# schematic1.net
KiCad netlist of a schematic drawn in EAGLE
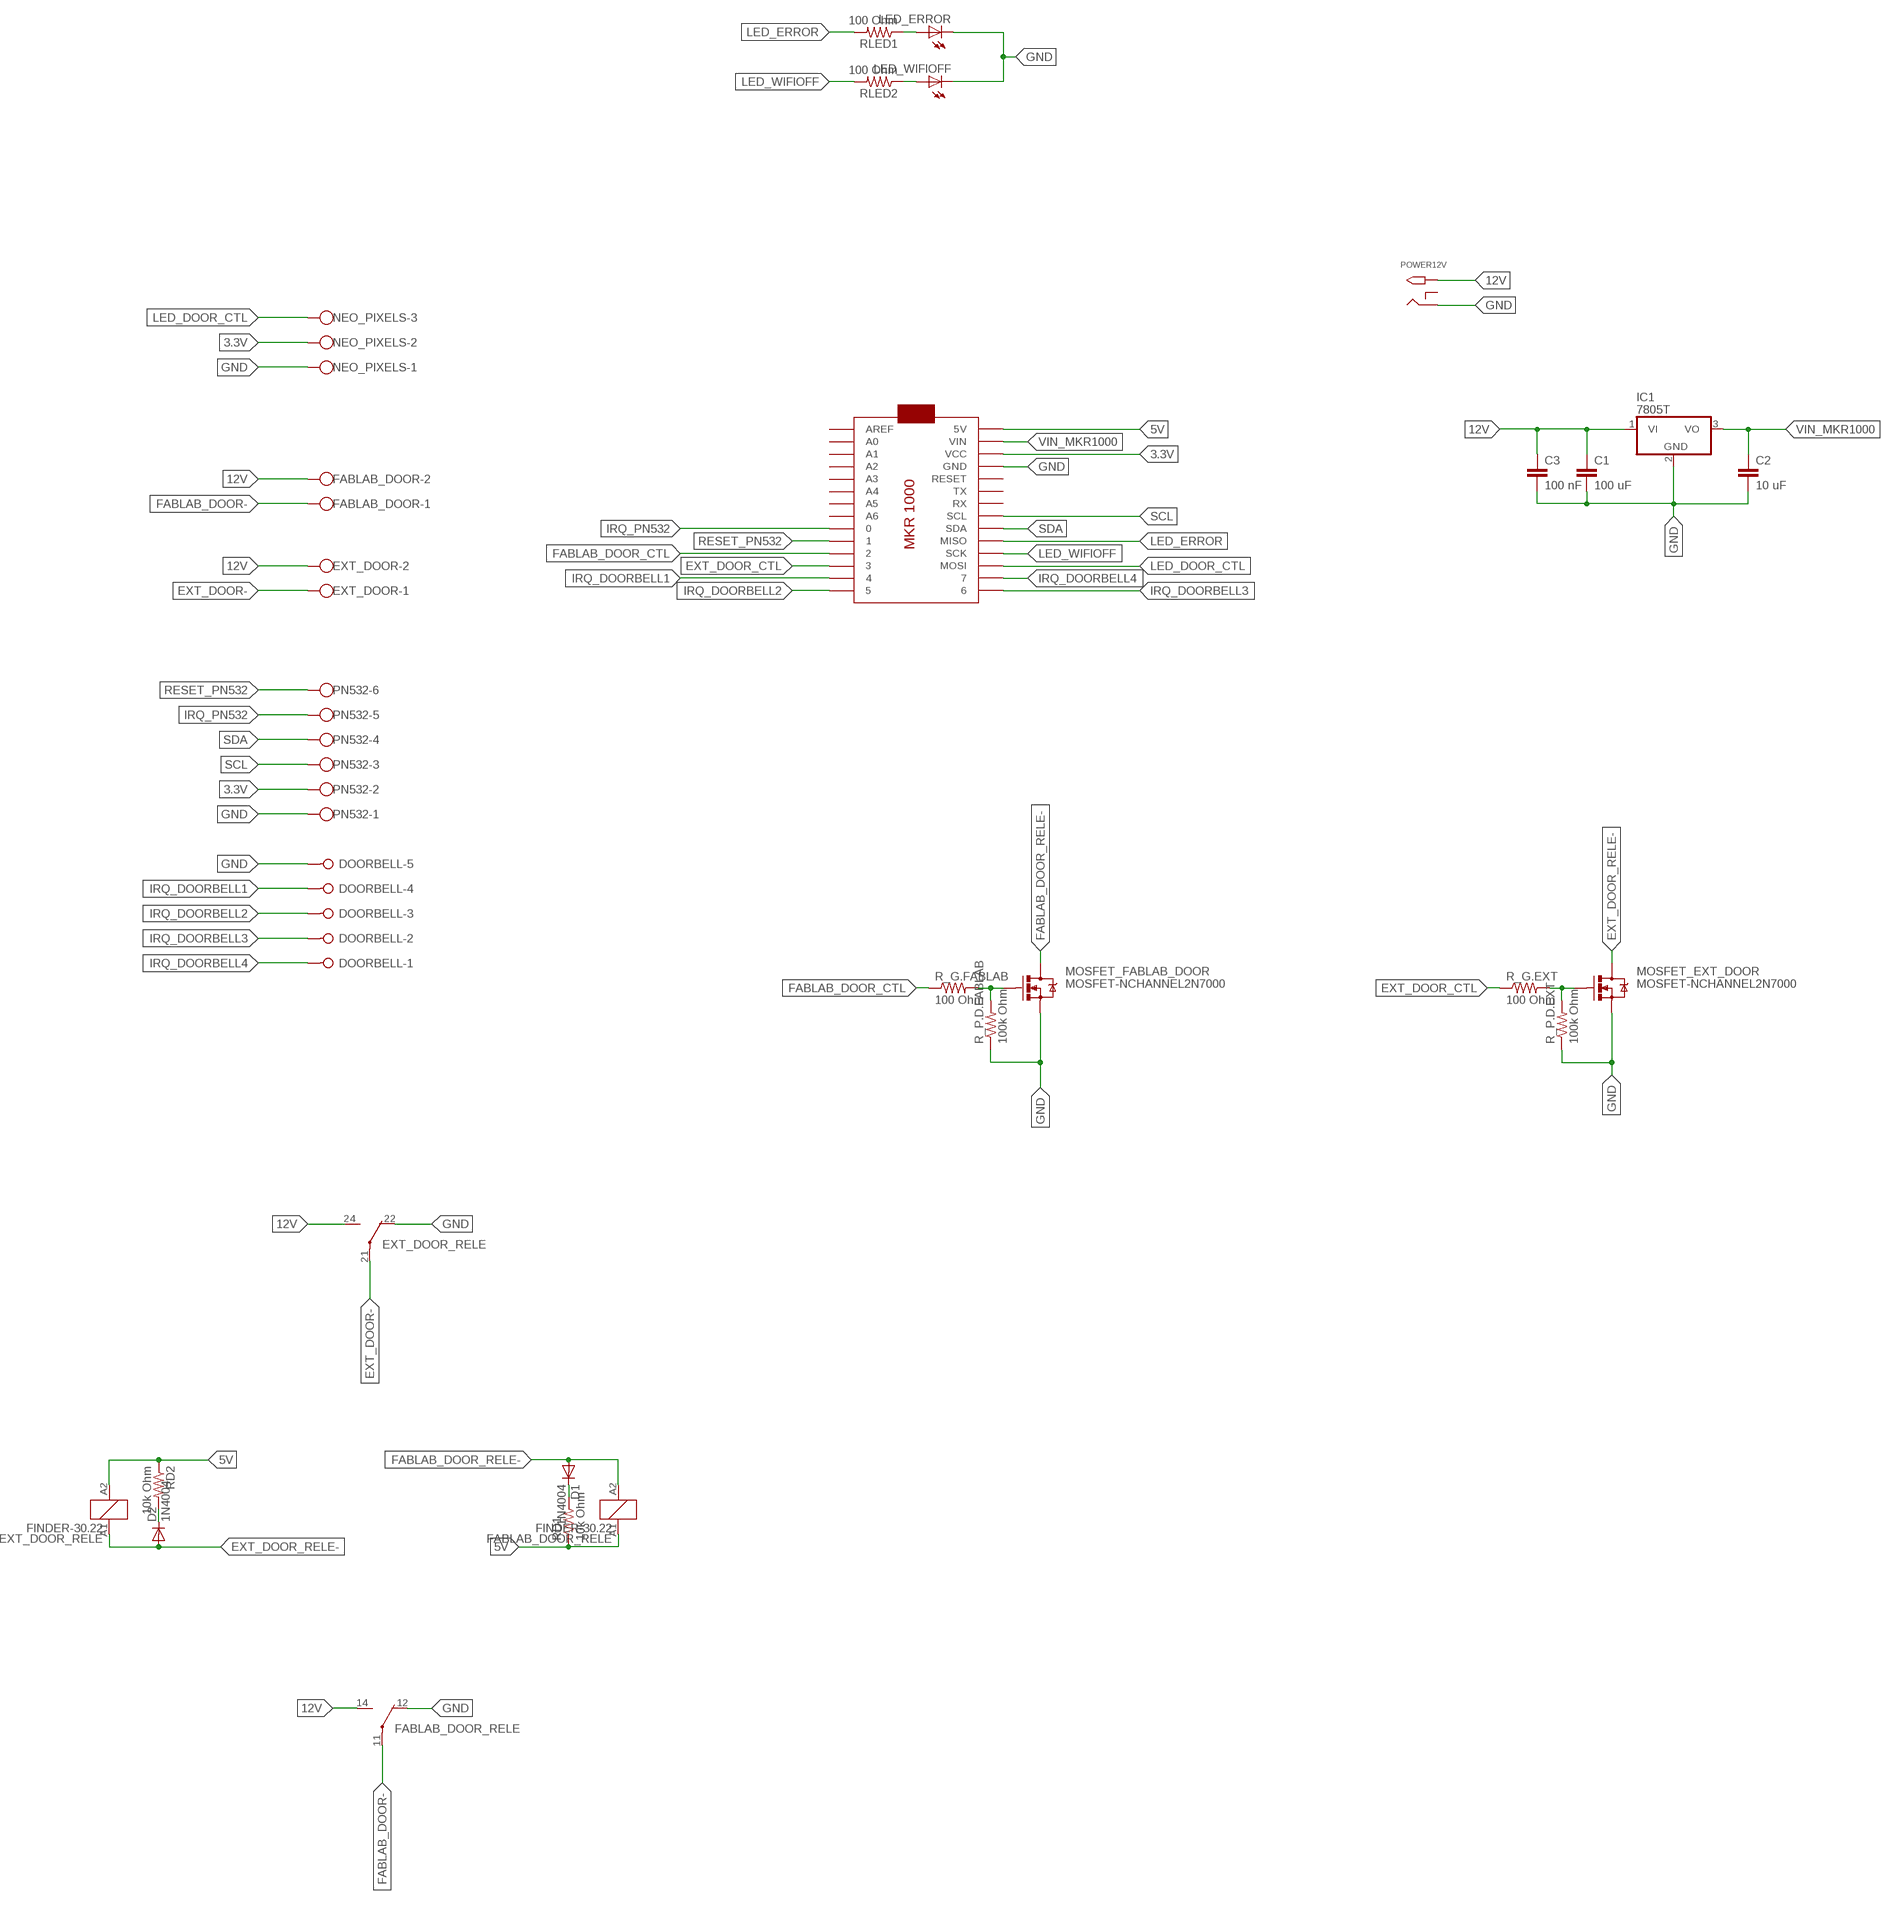
[diagram p0: schematic, sheet 1]

(export (version "E")
  (design (tool "Eeschema 10.0.6"))
  (components
    (comp (ref "C1")
      (value "100 uF")
      (footprint "eagle-import:C2.5-2")
      (libsource (lib "eagle-import") (part "C2.5/2"))
    )
    (comp (ref "C2")
      (value "10 uF")
      (footprint "eagle-import:C2.5-2")
      (libsource (lib "eagle-import") (part "C2.5/2"))
    )
    (comp (ref "C3")
      (value "100 nF")
      (footprint "eagle-import:C2.5-2")
      (libsource (lib "eagle-import") (part "C2.5/2"))
    )
    (comp (ref "D1")
      (value "1N4004")
      (footprint "eagle-import:DO41-10")
      (libsource (lib "eagle-import") (part "1N4004"))
    )
    (comp (ref "D2")
      (value "1N4004")
      (footprint "eagle-import:DO41-10")
      (libsource (lib "eagle-import") (part "1N4004"))
    )
    (comp (ref "DOORBELL")
      (value "W237-05P")
      (footprint "eagle-import:W237-5P")
      (libsource (lib "eagle-import") (part "W237-05P"))
    )
    (comp (ref "EXT_DOOR")
      (value "W237-102")
      (footprint "eagle-import:W237-102")
      (fields (field (name "MPN") "237-102"))
      (libsource (lib "eagle-import") (part "W237-102"))
    )
    (comp (ref "EXT_DOOR_RELE")
      (value "FINDER-30.22")
      (footprint "eagle-import:FINDER-30.22")
      (libsource (lib "eagle-import") (part "FINDER-30.22"))
    )
    (comp (ref "FABLAB_DOOR")
      (value "W237-102")
      (footprint "eagle-import:W237-102")
      (fields (field (name "MPN") "237-102"))
      (libsource (lib "eagle-import") (part "W237-102"))
    )
    (comp (ref "FABLAB_DOOR_RELE")
      (value "FINDER-30.22")
      (footprint "eagle-import:FINDER-30.22")
      (libsource (lib "eagle-import") (part "FINDER-30.22"))
    )
    (comp (ref "IC1")
      (value "7805T")
      (footprint "eagle-import:TO220H")
      (libsource (lib "eagle-import") (part "78T05"))
    )
    (comp (ref "LED_ERROR")
      (value "LED3MM")
      (footprint "eagle-import:LED3MM")
      (libsource (lib "eagle-import") (part "LED3MM"))
    )
    (comp (ref "LED_WIFIOFF")
      (value "LED3MM")
      (footprint "eagle-import:LED3MM")
      (libsource (lib "eagle-import") (part "LED3MM"))
    )
    (comp (ref "MOSFET_EXT_DOOR")
      (value "MOSFET-NCHANNEL2N7000")
      (footprint "eagle-import:TO-92")
      (libsource (lib "eagle-import") (part "MOSFET-NCHANNEL2N7000"))
    )
    (comp (ref "MOSFET_FABLAB_DOOR")
      (value "MOSFET-NCHANNEL2N7000")
      (footprint "eagle-import:TO-92")
      (libsource (lib "eagle-import") (part "MOSFET-NCHANNEL2N7000"))
    )
    (comp (ref "NEO_PIXELS")
      (value "W237-103")
      (footprint "eagle-import:W237-103")
      (fields (field (name "MPN") "237-103"))
      (libsource (lib "eagle-import") (part "W237-103"))
    )
    (comp (ref "PN532")
      (value "W237-136")
      (footprint "eagle-import:W237-136")
      (fields (field (name "MPN") "237-136"))
      (libsource (lib "eagle-import") (part "W237-136"))
    )
    (comp (ref "POWER12V")
      (value "2.1MMJACKTHM")
      (footprint "eagle-import:PJ-102A")
      (libsource (lib "eagle-import") (part "2.1MMJACKTHM"))
    )
    (comp (ref "RD1")
      (value "10k Ohm")
      (footprint "eagle-import:0207_10")
      (libsource (lib "eagle-import") (part "R-US_0207/10"))
    )
    (comp (ref "RD2")
      (value "10k Ohm")
      (footprint "eagle-import:0207_10")
      (libsource (lib "eagle-import") (part "R-US_0207/10"))
    )
    (comp (ref "RLED1")
      (value "100 Ohm")
      (footprint "eagle-import:0207_10")
      (libsource (lib "eagle-import") (part "R-US_0207/10"))
    )
    (comp (ref "RLED2")
      (value "100 Ohm")
      (footprint "eagle-import:0207_10")
      (libsource (lib "eagle-import") (part "R-US_0207/10"))
    )
    (comp (ref "R_G.EXT")
      (value "100 Ohm")
      (footprint "eagle-import:0207_10")
      (libsource (lib "eagle-import") (part "R-US_0207/10"))
    )
    (comp (ref "R_G.FABLAB")
      (value "100 Ohm")
      (footprint "eagle-import:0207_10")
      (libsource (lib "eagle-import") (part "R-US_0207/10"))
    )
    (comp (ref "R_P.D.EXT")
      (value "100k Ohm")
      (footprint "eagle-import:0207_10")
      (libsource (lib "eagle-import") (part "R-US_0207/10"))
    )
    (comp (ref "R_P.D.FABLAB")
      (value "100k Ohm")
      (footprint "eagle-import:0207_10")
      (libsource (lib "eagle-import") (part "R-US_0207/10"))
    )
    (comp (ref "U$1")
      (value "ARDUINOMKR1000")
      (footprint "eagle-import:ARDUINOMKR1000")
      (libsource (lib "eagle-import") (part "ARDUINOMKR1000"))
    )
  )
  (nets
    (net (code "1") (name "3.3V") (class "Default")
      (node (ref "NEO_PIXELS") (pin "2") (pinfunction "KL_2") (pintype "passive"))
      (node (ref "PN532") (pin "2") (pinfunction "KL_2") (pintype "passive"))
      (node (ref "U$1") (pin "VCC") (pinfunction "VCC_VCC") (pintype "bidirectional"))
    )
    (net (code "2") (name "5V") (class "Default")
      (node (ref "EXT_DOOR_RELE") (pin "A2") (pinfunction "2_A2") (pintype "passive"))
      (node (ref "FABLAB_DOOR_RELE") (pin "A1") (pinfunction "1_A1") (pintype "passive"))
      (node (ref "RD1") (pin "1") (pinfunction "1_1") (pintype "passive"))
      (node (ref "RD2") (pin "1") (pinfunction "1_1") (pintype "passive"))
      (node (ref "U$1") (pin "5V") (pinfunction "5V_5V") (pintype "bidirectional"))
    )
    (net (code "3") (name "12V") (class "Default")
      (node (ref "C1") (pin "1") (pinfunction "1_1") (pintype "passive"))
      (node (ref "C3") (pin "1") (pinfunction "1_1") (pintype "passive"))
      (node (ref "EXT_DOOR") (pin "2") (pinfunction "KL_2") (pintype "passive"))
      (node (ref "EXT_DOOR_RELE") (pin "24") (pinfunction "S_24") (pintype "passive"))
      (node (ref "FABLAB_DOOR") (pin "2") (pinfunction "KL_2") (pintype "passive"))
      (node (ref "FABLAB_DOOR_RELE") (pin "14") (pinfunction "S_14") (pintype "passive"))
      (node (ref "IC1") (pin "1") (pinfunction "VI_1") (pintype "input"))
      (node (ref "POWER12V") (pin "TIP") (pinfunction "TIP_TIP") (pintype "bidirectional"))
    )
    (net (code "4") (name "EXT_DOOR-") (class "Default")
      (node (ref "EXT_DOOR") (pin "1") (pinfunction "KL_1") (pintype "passive"))
      (node (ref "EXT_DOOR_RELE") (pin "21") (pinfunction "P_21") (pintype "passive"))
    )
    (net (code "5") (name "EXT_DOOR_CTL") (class "Default")
      (node (ref "R_G.EXT") (pin "1") (pinfunction "1_1") (pintype "passive"))
      (node (ref "U$1") (pin "3") (pinfunction "3_3") (pintype "bidirectional"))
    )
    (net (code "6") (name "EXT_DOOR_RELE-") (class "Default")
      (node (ref "D2") (pin "A") (pinfunction "A_A") (pintype "passive"))
      (node (ref "EXT_DOOR_RELE") (pin "A1") (pinfunction "1_A1") (pintype "passive"))
      (node (ref "MOSFET_EXT_DOOR") (pin "3") (pinfunction "D_3") (pintype "passive"))
    )
    (net (code "7") (name "FABLAB_DOOR-") (class "Default")
      (node (ref "FABLAB_DOOR") (pin "1") (pinfunction "KL_1") (pintype "passive"))
      (node (ref "FABLAB_DOOR_RELE") (pin "11") (pinfunction "P_11") (pintype "passive"))
    )
    (net (code "8") (name "FABLAB_DOOR_CTL") (class "Default")
      (node (ref "R_G.FABLAB") (pin "1") (pinfunction "1_1") (pintype "passive"))
      (node (ref "U$1") (pin "2") (pinfunction "2_2") (pintype "bidirectional"))
    )
    (net (code "9") (name "FABLAB_DOOR_RELE-") (class "Default")
      (node (ref "D1") (pin "A") (pinfunction "A_A") (pintype "passive"))
      (node (ref "FABLAB_DOOR_RELE") (pin "A2") (pinfunction "2_A2") (pintype "passive"))
      (node (ref "MOSFET_FABLAB_DOOR") (pin "3") (pinfunction "D_3") (pintype "passive"))
    )
    (net (code "10") (name "GND") (class "Default")
      (node (ref "C1") (pin "2") (pinfunction "2_2") (pintype "passive"))
      (node (ref "C2") (pin "2") (pinfunction "2_2") (pintype "passive"))
      (node (ref "C3") (pin "2") (pinfunction "2_2") (pintype "passive"))
      (node (ref "DOORBELL") (pin "5") (pinfunction "KL_5") (pintype "passive"))
      (node (ref "EXT_DOOR_RELE") (pin "22") (pinfunction "O_22") (pintype "passive"))
      (node (ref "FABLAB_DOOR_RELE") (pin "12") (pinfunction "O_12") (pintype "passive"))
      (node (ref "IC1") (pin "2") (pinfunction "GND_2") (pintype "passive"))
      (node (ref "LED_ERROR") (pin "K") (pinfunction "C_K") (pintype "passive"))
      (node (ref "LED_WIFIOFF") (pin "K") (pinfunction "C_K") (pintype "passive"))
      (node (ref "MOSFET_EXT_DOOR") (pin "1") (pinfunction "S_1") (pintype "passive"))
      (node (ref "MOSFET_FABLAB_DOOR") (pin "1") (pinfunction "S_1") (pintype "passive"))
      (node (ref "NEO_PIXELS") (pin "1") (pinfunction "KL_1") (pintype "passive"))
      (node (ref "PN532") (pin "1") (pinfunction "KL_1") (pintype "passive"))
      (node (ref "POWER12V") (pin "RING") (pinfunction "RING_RING") (pintype "bidirectional"))
      (node (ref "R_P.D.EXT") (pin "1") (pinfunction "1_1") (pintype "passive"))
      (node (ref "R_P.D.FABLAB") (pin "1") (pinfunction "1_1") (pintype "passive"))
      (node (ref "U$1") (pin "GND") (pinfunction "GND_GND") (pintype "bidirectional"))
    )
    (net (code "11") (name "IRQ_DOORBELL1") (class "Default")
      (node (ref "DOORBELL") (pin "4") (pinfunction "KL_4") (pintype "passive"))
      (node (ref "U$1") (pin "4") (pinfunction "4_4") (pintype "bidirectional"))
    )
    (net (code "12") (name "IRQ_DOORBELL2") (class "Default")
      (node (ref "DOORBELL") (pin "3") (pinfunction "KL_3") (pintype "passive"))
      (node (ref "U$1") (pin "5") (pinfunction "5_5") (pintype "bidirectional"))
    )
    (net (code "13") (name "IRQ_DOORBELL3") (class "Default")
      (node (ref "DOORBELL") (pin "2") (pinfunction "KL_2") (pintype "passive"))
      (node (ref "U$1") (pin "6") (pinfunction "6_6") (pintype "bidirectional"))
    )
    (net (code "14") (name "IRQ_DOORBELL4") (class "Default")
      (node (ref "DOORBELL") (pin "1") (pinfunction "KL_1") (pintype "passive"))
      (node (ref "U$1") (pin "7") (pinfunction "7_7") (pintype "bidirectional"))
    )
    (net (code "15") (name "IRQ_PN532") (class "Default")
      (node (ref "PN532") (pin "5") (pinfunction "KL_5") (pintype "passive"))
      (node (ref "U$1") (pin "0") (pinfunction "0_0") (pintype "bidirectional"))
    )
    (net (code "16") (name "LED_DOOR_CTL") (class "Default")
      (node (ref "NEO_PIXELS") (pin "3") (pinfunction "KL_3") (pintype "passive"))
      (node (ref "U$1") (pin "MOSI") (pinfunction "MOSI_MOSI") (pintype "bidirectional"))
    )
    (net (code "17") (name "LED_ERROR") (class "Default")
      (node (ref "RLED1") (pin "2") (pinfunction "2_2") (pintype "passive"))
      (node (ref "U$1") (pin "MISO") (pinfunction "MISO_MISO") (pintype "bidirectional"))
    )
    (net (code "18") (name "LED_WIFIOFF") (class "Default")
      (node (ref "RLED2") (pin "2") (pinfunction "2_2") (pintype "passive"))
      (node (ref "U$1") (pin "SCK") (pinfunction "SCK_SCK") (pintype "bidirectional"))
    )
    (net (code "19") (name "Net-(D1-PadC)") (class "Default")
      (node (ref "D1") (pin "C") (pinfunction "C_C") (pintype "passive"))
      (node (ref "RD1") (pin "2") (pinfunction "2_2") (pintype "passive"))
    )
    (net (code "20") (name "Net-(D2-PadC)") (class "Default")
      (node (ref "D2") (pin "C") (pinfunction "C_C") (pintype "passive"))
      (node (ref "RD2") (pin "2") (pinfunction "2_2") (pintype "passive"))
    )
    (net (code "21") (name "Net-(LED_ERROR-PadA)") (class "Default")
      (node (ref "LED_ERROR") (pin "A") (pinfunction "A_A") (pintype "passive"))
      (node (ref "RLED1") (pin "1") (pinfunction "1_1") (pintype "passive"))
    )
    (net (code "22") (name "Net-(LED_WIFIOFF-PadA)") (class "Default")
      (node (ref "LED_WIFIOFF") (pin "A") (pinfunction "A_A") (pintype "passive"))
      (node (ref "RLED2") (pin "1") (pinfunction "1_1") (pintype "passive"))
    )
    (net (code "23") (name "Net-(MOSFET_EXT_DOOR-G)") (class "Default")
      (node (ref "MOSFET_EXT_DOOR") (pin "2") (pinfunction "G_2") (pintype "passive"))
      (node (ref "R_G.EXT") (pin "2") (pinfunction "2_2") (pintype "passive"))
      (node (ref "R_P.D.EXT") (pin "2") (pinfunction "2_2") (pintype "passive"))
    )
    (net (code "24") (name "Net-(MOSFET_FABLAB_DOOR-G)") (class "Default")
      (node (ref "MOSFET_FABLAB_DOOR") (pin "2") (pinfunction "G_2") (pintype "passive"))
      (node (ref "R_G.FABLAB") (pin "2") (pinfunction "2_2") (pintype "passive"))
      (node (ref "R_P.D.FABLAB") (pin "2") (pinfunction "2_2") (pintype "passive"))
    )
    (net (code "25") (name "RESET_PN532") (class "Default")
      (node (ref "PN532") (pin "6") (pinfunction "KL_6") (pintype "passive"))
      (node (ref "U$1") (pin "1") (pinfunction "1_1") (pintype "bidirectional"))
    )
    (net (code "26") (name "SCL") (class "Default")
      (node (ref "PN532") (pin "3") (pinfunction "KL_3") (pintype "passive"))
      (node (ref "U$1") (pin "SCL") (pinfunction "SCL_SCL") (pintype "bidirectional"))
    )
    (net (code "27") (name "SDA") (class "Default")
      (node (ref "PN532") (pin "4") (pinfunction "KL_4") (pintype "passive"))
      (node (ref "U$1") (pin "SDA") (pinfunction "SDA_SDA") (pintype "bidirectional"))
    )
    (net (code "28") (name "VIN_MKR1000") (class "Default")
      (node (ref "C2") (pin "1") (pinfunction "1_1") (pintype "passive"))
      (node (ref "IC1") (pin "3") (pinfunction "VO_3") (pintype "passive"))
      (node (ref "U$1") (pin "VIN") (pinfunction "VIN_VIN") (pintype "bidirectional"))
    )
    (net (code "29") (name "unconnected-(POWER12V-PadRING_SW)") (class "Default")
      (node (ref "POWER12V") (pin "RING_SW") (pinfunction "RING_SW_RING_SW") (pintype "bidirectional"))
    )
    (net (code "30") (name "unconnected-(U$1-PadA0)") (class "Default")
      (node (ref "U$1") (pin "A0") (pinfunction "A0_A0") (pintype "bidirectional"))
    )
    (net (code "31") (name "unconnected-(U$1-PadA1)") (class "Default")
      (node (ref "U$1") (pin "A1") (pinfunction "A1_A1") (pintype "bidirectional"))
    )
    (net (code "32") (name "unconnected-(U$1-PadA2)") (class "Default")
      (node (ref "U$1") (pin "A2") (pinfunction "A2_A2") (pintype "bidirectional"))
    )
    (net (code "33") (name "unconnected-(U$1-PadA3)") (class "Default")
      (node (ref "U$1") (pin "A3") (pinfunction "A3_A3") (pintype "bidirectional"))
    )
    (net (code "34") (name "unconnected-(U$1-PadA4)") (class "Default")
      (node (ref "U$1") (pin "A4") (pinfunction "A4_A4") (pintype "bidirectional"))
    )
    (net (code "35") (name "unconnected-(U$1-PadA5)") (class "Default")
      (node (ref "U$1") (pin "A5") (pinfunction "A5_A5") (pintype "bidirectional"))
    )
    (net (code "36") (name "unconnected-(U$1-PadA6)") (class "Default")
      (node (ref "U$1") (pin "A6") (pinfunction "A6_A6") (pintype "bidirectional"))
    )
    (net (code "37") (name "unconnected-(U$1-PadAREF)") (class "Default")
      (node (ref "U$1") (pin "AREF") (pinfunction "AREF_AREF") (pintype "bidirectional"))
    )
    (net (code "38") (name "unconnected-(U$1-PadRESET)") (class "Default")
      (node (ref "U$1") (pin "RESET") (pinfunction "RESET_RESET") (pintype "bidirectional"))
    )
    (net (code "39") (name "unconnected-(U$1-PadRX)") (class "Default")
      (node (ref "U$1") (pin "RX") (pinfunction "RX_RX") (pintype "bidirectional"))
    )
    (net (code "40") (name "unconnected-(U$1-PadTX)") (class "Default")
      (node (ref "U$1") (pin "TX") (pinfunction "TX_TX") (pintype "bidirectional"))
    )
  )
)
